# Schematic_CAN2USB.net
KiCad netlist of a schematic drawn in Altium Designer
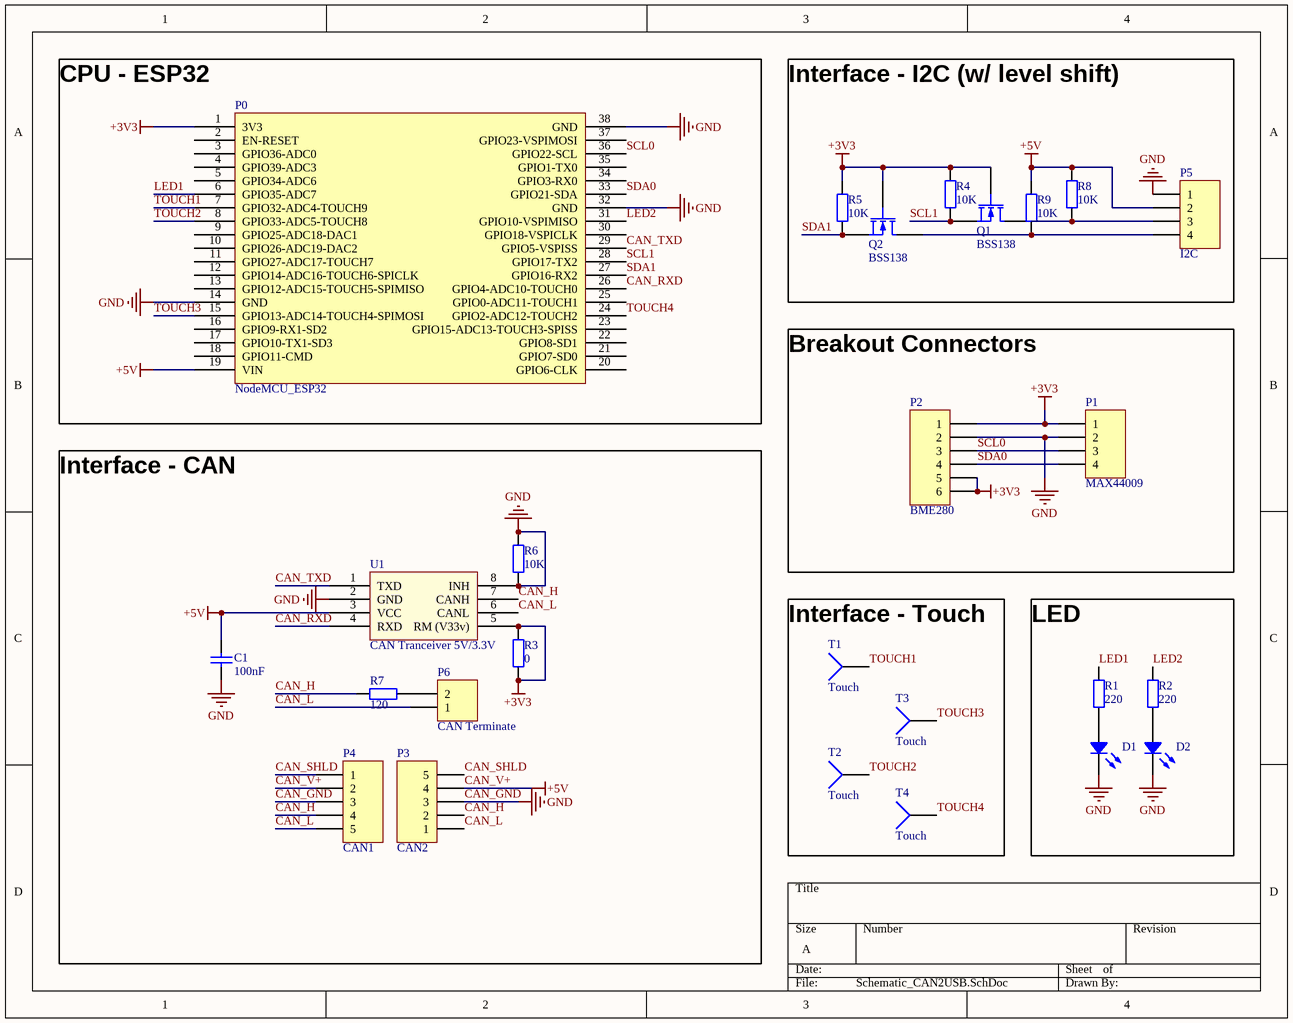
[diagram p0: Schematic_CAN2USB.SchDoc]

(export (version "E")
  (design (tool "Eeschema 10.0.6"))
  (components
    (comp (ref "C1")
      (value "100nF")
      (footprint "CAP 0805/2012")
      (description "Capacitor")
      (fields (field (name "Comment") "Cap") (field (name "PUBLISHER") "Altium Limited"))
      (libsource (lib "Miscellaneous Devices") (part "Cap"))
    )
    (comp (ref "D1")
      (value "Green")
      (footprint "LED 0805/2012 RED")
      (description "Chip LED")
      (libsource (lib "Diodes") (part "LED"))
    )
    (comp (ref "D2")
      (value "Green")
      (footprint "LED 0805/2012 RED")
      (description "Chip LED")
      (libsource (lib "Diodes") (part "LED"))
    )
    (comp (ref "P0")
      (value "NodeMCU_ESP32")
      (footprint "NodeMCU")
      (libsource (lib "SchLib_CAN2USB") (part "NodeMCU_ESP32"))
    )
    (comp (ref "P1")
      (value "MAX44009")
      (footprint "MAX44009_Breakout")
      (description "Header, 4-Pin")
      (fields (field (name "PUBLISHER") "Altium Limited"))
      (libsource (lib "Miscellaneous Connectors") (part "Header 4"))
    )
    (comp (ref "P2")
      (value "BME280")
      (footprint "BME280_Breakout")
      (description "Header, 6-Pin")
      (fields (field (name "PUBLISHER") "Altium Limited"))
      (libsource (lib "Miscellaneous Connectors") (part "Header 6"))
    )
    (comp (ref "P3")
      (value "CAN2")
      (footprint "TE 282834-5")
      (description "Header, 5-Pin")
      (fields (field (name "PUBLISHER") "Altium Limited"))
      (libsource (lib "") (part "Header 5_1"))
    )
    (comp (ref "P4")
      (value "CAN1")
      (footprint "TE 282834-5")
      (description "Header, 5-Pin")
      (fields (field (name "PUBLISHER") "Altium Limited"))
      (libsource (lib "Miscellaneous Connectors") (part "Header 5"))
    )
    (comp (ref "P5")
      (value "I2C")
      (footprint "TE 282834-4")
      (description "Header, 4-Pin")
      (fields (field (name "PUBLISHER") "Altium Limited"))
      (libsource (lib "Miscellaneous Connectors") (part "Header 4"))
    )
    (comp (ref "P6")
      (value "CAN Terminate")
      (footprint "SAMTEC SSW-102-03-T-S")
      (description "Header, 2-Pin")
      (fields (field (name "PUBLISHER") "Altium Limited"))
      (libsource (lib "Miscellaneous Connectors") (part "Header 2"))
    )
    (comp (ref "Q1")
      (value "BSS138")
      (footprint "DIODES SOT-23-3")
      (description "N-Channel MOSFET")
      (fields (field (name "PUBLISHER") "Altium Limited"))
      (libsource (lib "Miscellaneous Devices") (part "MOSFET-N"))
    )
    (comp (ref "Q2")
      (value "BSS138")
      (footprint "DIODES SOT-23-3")
      (description "N-Channel MOSFET")
      (fields (field (name "PUBLISHER") "Altium Limited"))
      (libsource (lib "Miscellaneous Devices") (part "MOSFET-N"))
    )
    (comp (ref "R1")
      (value "220")
      (footprint "RES 0805/2012")
      (description "Resistor")
      (fields (field (name "Comment") "Res2") (field (name "PUBLISHER") "Altium Limited"))
      (libsource (lib "Miscellaneous Devices") (part "Res2"))
    )
    (comp (ref "R2")
      (value "220")
      (footprint "RES 0805/2012")
      (description "Resistor")
      (fields (field (name "Comment") "Res2") (field (name "PUBLISHER") "Altium Limited"))
      (libsource (lib "Miscellaneous Devices") (part "Res2"))
    )
    (comp (ref "R3")
      (value "0")
      (footprint "RES 0805/2012")
      (description "Resistor")
      (fields (field (name "Comment") "Res2") (field (name "PUBLISHER") "Altium Limited"))
      (libsource (lib "Miscellaneous Devices") (part "Res2"))
    )
    (comp (ref "R4")
      (value "10K")
      (footprint "RES 0805/2012")
      (description "Resistor")
      (fields (field (name "Comment") "Res2") (field (name "PUBLISHER") "Altium Limited"))
      (libsource (lib "Miscellaneous Devices") (part "Res2"))
    )
    (comp (ref "R5")
      (value "10K")
      (footprint "RES 0805/2012")
      (description "Resistor")
      (fields (field (name "Comment") "Res2") (field (name "PUBLISHER") "Altium Limited"))
      (libsource (lib "Miscellaneous Devices") (part "Res2"))
    )
    (comp (ref "R6")
      (value "10K")
      (footprint "RES 0805/2012")
      (description "Resistor")
      (fields (field (name "Comment") "Res2") (field (name "PUBLISHER") "Altium Limited"))
      (libsource (lib "Miscellaneous Devices") (part "Res2"))
    )
    (comp (ref "R7")
      (value "120")
      (footprint "RES 0805/2012")
      (description "Resistor")
      (fields (field (name "Comment") "Res2") (field (name "PUBLISHER") "Altium Limited"))
      (libsource (lib "") (part "Res2_1"))
    )
    (comp (ref "R8")
      (value "10K")
      (footprint "RES 0805/2012")
      (description "Resistor")
      (fields (field (name "Comment") "Res2") (field (name "PUBLISHER") "Altium Limited"))
      (libsource (lib "Miscellaneous Devices") (part "Res2"))
    )
    (comp (ref "R9")
      (value "10K")
      (footprint "RES 0805/2012")
      (description "Resistor")
      (fields (field (name "Comment") "Res2") (field (name "PUBLISHER") "Altium Limited"))
      (libsource (lib "Miscellaneous Devices") (part "Res2"))
    )
    (comp (ref "T1")
      (value "Touch")
      (footprint "Pad")
      (description "Socket")
      (fields (field (name "PUBLISHER") "Altium Limited"))
      (libsource (lib "Miscellaneous Connectors") (part "Socket"))
    )
    (comp (ref "T2")
      (value "Touch")
      (footprint "Pad")
      (description "Socket")
      (fields (field (name "PUBLISHER") "Altium Limited"))
      (libsource (lib "Miscellaneous Connectors") (part "Socket"))
    )
    (comp (ref "T3")
      (value "Touch")
      (footprint "Pad")
      (description "Socket")
      (fields (field (name "PUBLISHER") "Altium Limited"))
      (libsource (lib "Miscellaneous Connectors") (part "Socket"))
    )
    (comp (ref "T4")
      (value "Touch")
      (footprint "Pad")
      (description "Socket")
      (fields (field (name "PUBLISHER") "Altium Limited"))
      (libsource (lib "Miscellaneous Connectors") (part "Socket"))
    )
    (comp (ref "U1")
      (value "CAN Tranceiver 5V/3.3V")
      (footprint "MICROCHIP SOIC-8 150mil Wide")
      (libsource (lib "GJ24") (part "TLE6250G(V33)"))
    )
  )
  (nets
    (net (code "1") (name "+3V3") (class "Default")
      (node (ref "P0") (pin "1") (pinfunction "3V3_1") (pintype "passive"))
      (node (ref "P1") (pin "1") (pinfunction "1_1") (pintype "passive"))
      (node (ref "P2") (pin "1") (pinfunction "1_1") (pintype "passive"))
      (node (ref "P2") (pin "5") (pinfunction "5_5") (pintype "passive"))
      (node (ref "P2") (pin "6") (pinfunction "6_6") (pintype "passive"))
      (node (ref "Q1") (pin "2") (pinfunction "G_2") (pintype "passive"))
      (node (ref "Q2") (pin "2") (pinfunction "G_2") (pintype "passive"))
      (node (ref "R3") (pin "1") (pinfunction "1_1") (pintype "passive"))
      (node (ref "R3") (pin "2") (pinfunction "2_2") (pintype "passive"))
      (node (ref "R4") (pin "2") (pinfunction "2_2") (pintype "passive"))
      (node (ref "R5") (pin "2") (pinfunction "2_2") (pintype "passive"))
      (node (ref "U1") (pin "5") (pinfunction "RM_(V33v)_5") (pintype "passive"))
    )
    (net (code "2") (name "+5V") (class "Default")
      (node (ref "C1") (pin "1") (pinfunction "1_1") (pintype "passive"))
      (node (ref "P0") (pin "19") (pinfunction "VIN_19") (pintype "passive"))
      (node (ref "P3") (pin "4") (pinfunction "4_4") (pintype "passive"))
      (node (ref "P4") (pin "2") (pinfunction "2_2") (pintype "passive"))
      (node (ref "P5") (pin "2") (pinfunction "2_2") (pintype "passive"))
      (node (ref "R8") (pin "2") (pinfunction "2_2") (pintype "passive"))
      (node (ref "R9") (pin "2") (pinfunction "2_2") (pintype "passive"))
      (node (ref "U1") (pin "3") (pinfunction "VCC_3") (pintype "passive"))
    )
    (net (code "3") (name "/CAN_H") (class "Default")
      (node (ref "P3") (pin "2") (pinfunction "2_2") (pintype "passive"))
      (node (ref "P4") (pin "4") (pinfunction "4_4") (pintype "passive"))
      (node (ref "R7") (pin "2") (pinfunction "2_2") (pintype "passive"))
      (node (ref "U1") (pin "7") (pinfunction "CANH_7") (pintype "passive"))
    )
    (net (code "4") (name "/CAN_L") (class "Default")
      (node (ref "P3") (pin "1") (pinfunction "1_1") (pintype "passive"))
      (node (ref "P4") (pin "5") (pinfunction "5_5") (pintype "passive"))
      (node (ref "P6") (pin "1") (pinfunction "1_1") (pintype "passive"))
      (node (ref "U1") (pin "6") (pinfunction "CANL_6") (pintype "passive"))
    )
    (net (code "5") (name "/CAN_RXD") (class "Default")
      (node (ref "P0") (pin "26") (pinfunction "GPIO4-ADC10-TOUCH0_26") (pintype "passive"))
      (node (ref "U1") (pin "4") (pinfunction "RXD_4") (pintype "passive"))
    )
    (net (code "6") (name "/CAN_SHLD") (class "Default")
      (node (ref "P3") (pin "5") (pinfunction "5_5") (pintype "passive"))
      (node (ref "P4") (pin "1") (pinfunction "1_1") (pintype "passive"))
    )
    (net (code "7") (name "/CAN_TXD") (class "Default")
      (node (ref "P0") (pin "29") (pinfunction "GPIO5-VSPISS_29") (pintype "passive"))
      (node (ref "U1") (pin "1") (pinfunction "TXD_1") (pintype "passive"))
    )
    (net (code "8") (name "/LED1") (class "Default")
      (node (ref "P0") (pin "6") (pinfunction "GPIO35-ADC7_6") (pintype "passive"))
      (node (ref "R1") (pin "2") (pinfunction "2_2") (pintype "passive"))
    )
    (net (code "9") (name "/LED2") (class "Default")
      (node (ref "P0") (pin "31") (pinfunction "GPIO10-VSPIMISO_31") (pintype "passive"))
      (node (ref "R2") (pin "2") (pinfunction "2_2") (pintype "passive"))
    )
    (net (code "10") (name "/SCL0") (class "Default")
      (node (ref "P0") (pin "36") (pinfunction "GPIO22-SCL_36") (pintype "passive"))
      (node (ref "P1") (pin "3") (pinfunction "3_3") (pintype "passive"))
      (node (ref "P2") (pin "3") (pinfunction "3_3") (pintype "passive"))
    )
    (net (code "11") (name "/SCL1") (class "Default")
      (node (ref "P0") (pin "28") (pinfunction "GPIO17-TX2_28") (pintype "passive"))
      (node (ref "Q1") (pin "3") (pinfunction "S_3") (pintype "passive"))
      (node (ref "R4") (pin "1") (pinfunction "1_1") (pintype "passive"))
    )
    (net (code "12") (name "/SDA0") (class "Default")
      (node (ref "P0") (pin "33") (pinfunction "GPIO21-SDA_33") (pintype "passive"))
      (node (ref "P1") (pin "4") (pinfunction "4_4") (pintype "passive"))
      (node (ref "P2") (pin "4") (pinfunction "4_4") (pintype "passive"))
    )
    (net (code "13") (name "/SDA1") (class "Default")
      (node (ref "P0") (pin "27") (pinfunction "GPIO16-RX2_27") (pintype "passive"))
      (node (ref "Q2") (pin "3") (pinfunction "S_3") (pintype "passive"))
      (node (ref "R5") (pin "1") (pinfunction "1_1") (pintype "passive"))
    )
    (net (code "14") (name "/TOUCH1") (class "Default")
      (node (ref "P0") (pin "7") (pinfunction "GPIO32-ADC4-TOUCH9_7") (pintype "passive"))
      (node (ref "T1") (pin "1") (pinfunction "1_1") (pintype "passive"))
    )
    (net (code "15") (name "/TOUCH2") (class "Default")
      (node (ref "P0") (pin "8") (pinfunction "GPIO33-ADC5-TOUCH8_8") (pintype "passive"))
      (node (ref "T2") (pin "1") (pinfunction "1_1") (pintype "passive"))
    )
    (net (code "16") (name "/TOUCH3") (class "Default")
      (node (ref "P0") (pin "15") (pinfunction "GPIO13-ADC14-TOUCH4-SPIMOSI_15") (pintype "passive"))
      (node (ref "T3") (pin "1") (pinfunction "1_1") (pintype "passive"))
    )
    (net (code "17") (name "/TOUCH4") (class "Default")
      (node (ref "P0") (pin "24") (pinfunction "GPIO2-ADC12-TOUCH2_24") (pintype "passive"))
      (node (ref "T4") (pin "1") (pinfunction "1_1") (pintype "passive"))
    )
    (net (code "18") (name "GND") (class "Default")
      (node (ref "C1") (pin "2") (pinfunction "2_2") (pintype "passive"))
      (node (ref "D1") (pin "2") (pinfunction "2_2") (pintype "passive"))
      (node (ref "D2") (pin "2") (pinfunction "2_2") (pintype "passive"))
      (node (ref "P0") (pin "14") (pinfunction "GND_14") (pintype "passive"))
      (node (ref "P0") (pin "32") (pinfunction "GND_32") (pintype "passive"))
      (node (ref "P0") (pin "38") (pinfunction "GND_38") (pintype "passive"))
      (node (ref "P1") (pin "2") (pinfunction "2_2") (pintype "passive"))
      (node (ref "P2") (pin "2") (pinfunction "2_2") (pintype "passive"))
      (node (ref "P3") (pin "3") (pinfunction "3_3") (pintype "passive"))
      (node (ref "P4") (pin "3") (pinfunction "3_3") (pintype "passive"))
      (node (ref "P5") (pin "1") (pinfunction "1_1") (pintype "passive"))
      (node (ref "R6") (pin "1") (pinfunction "1_1") (pintype "passive"))
      (node (ref "R6") (pin "2") (pinfunction "2_2") (pintype "passive"))
      (node (ref "U1") (pin "2") (pinfunction "GND_2") (pintype "passive"))
      (node (ref "U1") (pin "8") (pinfunction "INH_8") (pintype "passive"))
    )
    (net (code "19") (name "Net-(D1-Pad1)") (class "Default")
      (node (ref "D1") (pin "1") (pinfunction "1_1") (pintype "passive"))
      (node (ref "R1") (pin "1") (pinfunction "1_1") (pintype "passive"))
    )
    (net (code "20") (name "Net-(D2-Pad1)") (class "Default")
      (node (ref "D2") (pin "1") (pinfunction "1_1") (pintype "passive"))
      (node (ref "R2") (pin "1") (pinfunction "1_1") (pintype "passive"))
    )
    (net (code "21") (name "Net-(P6-Pad2)") (class "Default")
      (node (ref "P6") (pin "2") (pinfunction "2_2") (pintype "passive"))
      (node (ref "R7") (pin "1") (pinfunction "1_1") (pintype "passive"))
    )
    (net (code "22") (name "Net-(Q1-D)") (class "Default")
      (node (ref "P5") (pin "3") (pinfunction "3_3") (pintype "passive"))
      (node (ref "Q1") (pin "1") (pinfunction "D_1") (pintype "passive"))
      (node (ref "R8") (pin "1") (pinfunction "1_1") (pintype "passive"))
    )
    (net (code "23") (name "Net-(Q2-D)") (class "Default")
      (node (ref "P5") (pin "4") (pinfunction "4_4") (pintype "passive"))
      (node (ref "Q2") (pin "1") (pinfunction "D_1") (pintype "passive"))
      (node (ref "R9") (pin "1") (pinfunction "1_1") (pintype "passive"))
    )
    (net (code "24") (name "unconnected-(P0-EN-RESET-Pad2)") (class "Default")
      (node (ref "P0") (pin "2") (pinfunction "EN-RESET_2") (pintype "passive"))
    )
    (net (code "25") (name "unconnected-(P0-GPIO0-ADC11-TOUCH1-Pad25)") (class "Default")
      (node (ref "P0") (pin "25") (pinfunction "GPIO0-ADC11-TOUCH1_25") (pintype "passive"))
    )
    (net (code "26") (name "unconnected-(P0-GPIO1-TX0-Pad35)") (class "Default")
      (node (ref "P0") (pin "35") (pinfunction "GPIO1-TX0_35") (pintype "passive"))
    )
    (net (code "27") (name "unconnected-(P0-GPIO3-RX0-Pad34)") (class "Default")
      (node (ref "P0") (pin "34") (pinfunction "GPIO3-RX0_34") (pintype "passive"))
    )
    (net (code "28") (name "unconnected-(P0-GPIO6-CLK-Pad20)") (class "Default")
      (node (ref "P0") (pin "20") (pinfunction "GPIO6-CLK_20") (pintype "passive"))
    )
    (net (code "29") (name "unconnected-(P0-GPIO7-SD0-Pad21)") (class "Default")
      (node (ref "P0") (pin "21") (pinfunction "GPIO7-SD0_21") (pintype "passive"))
    )
    (net (code "30") (name "unconnected-(P0-GPIO8-SD1-Pad22)") (class "Default")
      (node (ref "P0") (pin "22") (pinfunction "GPIO8-SD1_22") (pintype "passive"))
    )
    (net (code "31") (name "unconnected-(P0-GPIO9-RX1-SD2-Pad16)") (class "Default")
      (node (ref "P0") (pin "16") (pinfunction "GPIO9-RX1-SD2_16") (pintype "passive"))
    )
    (net (code "32") (name "unconnected-(P0-GPIO10-TX1-SD3-Pad17)") (class "Default")
      (node (ref "P0") (pin "17") (pinfunction "GPIO10-TX1-SD3_17") (pintype "passive"))
    )
    (net (code "33") (name "unconnected-(P0-GPIO11-CMD-Pad18)") (class "Default")
      (node (ref "P0") (pin "18") (pinfunction "GPIO11-CMD_18") (pintype "passive"))
    )
    (net (code "34") (name "unconnected-(P0-GPIO12-ADC15-TOUCH5-SPIMISO-Pad13)") (class "Default")
      (node (ref "P0") (pin "13") (pinfunction "GPIO12-ADC15-TOUCH5-SPIMISO_13") (pintype "passive"))
    )
    (net (code "35") (name "unconnected-(P0-GPIO14-ADC16-TOUCH6-SPICLK-Pad12)") (class "Default")
      (node (ref "P0") (pin "12") (pinfunction "GPIO14-ADC16-TOUCH6-SPICLK_12") (pintype "passive"))
    )
    (net (code "36") (name "unconnected-(P0-GPIO15-ADC13-TOUCH3-SPISS-Pad23)") (class "Default")
      (node (ref "P0") (pin "23") (pinfunction "GPIO15-ADC13-TOUCH3-SPISS_23") (pintype "passive"))
    )
    (net (code "37") (name "unconnected-(P0-GPIO18-VSPICLK-Pad30)") (class "Default")
      (node (ref "P0") (pin "30") (pinfunction "GPIO18-VSPICLK_30") (pintype "passive"))
    )
    (net (code "38") (name "unconnected-(P0-GPIO23-VSPIMOSI-Pad37)") (class "Default")
      (node (ref "P0") (pin "37") (pinfunction "GPIO23-VSPIMOSI_37") (pintype "passive"))
    )
    (net (code "39") (name "unconnected-(P0-GPIO25-ADC18-DAC1-Pad9)") (class "Default")
      (node (ref "P0") (pin "9") (pinfunction "GPIO25-ADC18-DAC1_9") (pintype "passive"))
    )
    (net (code "40") (name "unconnected-(P0-GPIO26-ADC19-DAC2-Pad10)") (class "Default")
      (node (ref "P0") (pin "10") (pinfunction "GPIO26-ADC19-DAC2_10") (pintype "passive"))
    )
    (net (code "41") (name "unconnected-(P0-GPIO27-ADC17-TOUCH7-Pad11)") (class "Default")
      (node (ref "P0") (pin "11") (pinfunction "GPIO27-ADC17-TOUCH7_11") (pintype "passive"))
    )
    (net (code "42") (name "unconnected-(P0-GPIO34-ADC6-Pad5)") (class "Default")
      (node (ref "P0") (pin "5") (pinfunction "GPIO34-ADC6_5") (pintype "passive"))
    )
    (net (code "43") (name "unconnected-(P0-GPIO36-ADC0-Pad3)") (class "Default")
      (node (ref "P0") (pin "3") (pinfunction "GPIO36-ADC0_3") (pintype "passive"))
    )
    (net (code "44") (name "unconnected-(P0-GPIO39-ADC3-Pad4)") (class "Default")
      (node (ref "P0") (pin "4") (pinfunction "GPIO39-ADC3_4") (pintype "passive"))
    )
  )
)
